# Digital_STMG474RE.net
KiCad netlist of a schematic drawn in Altium Designer
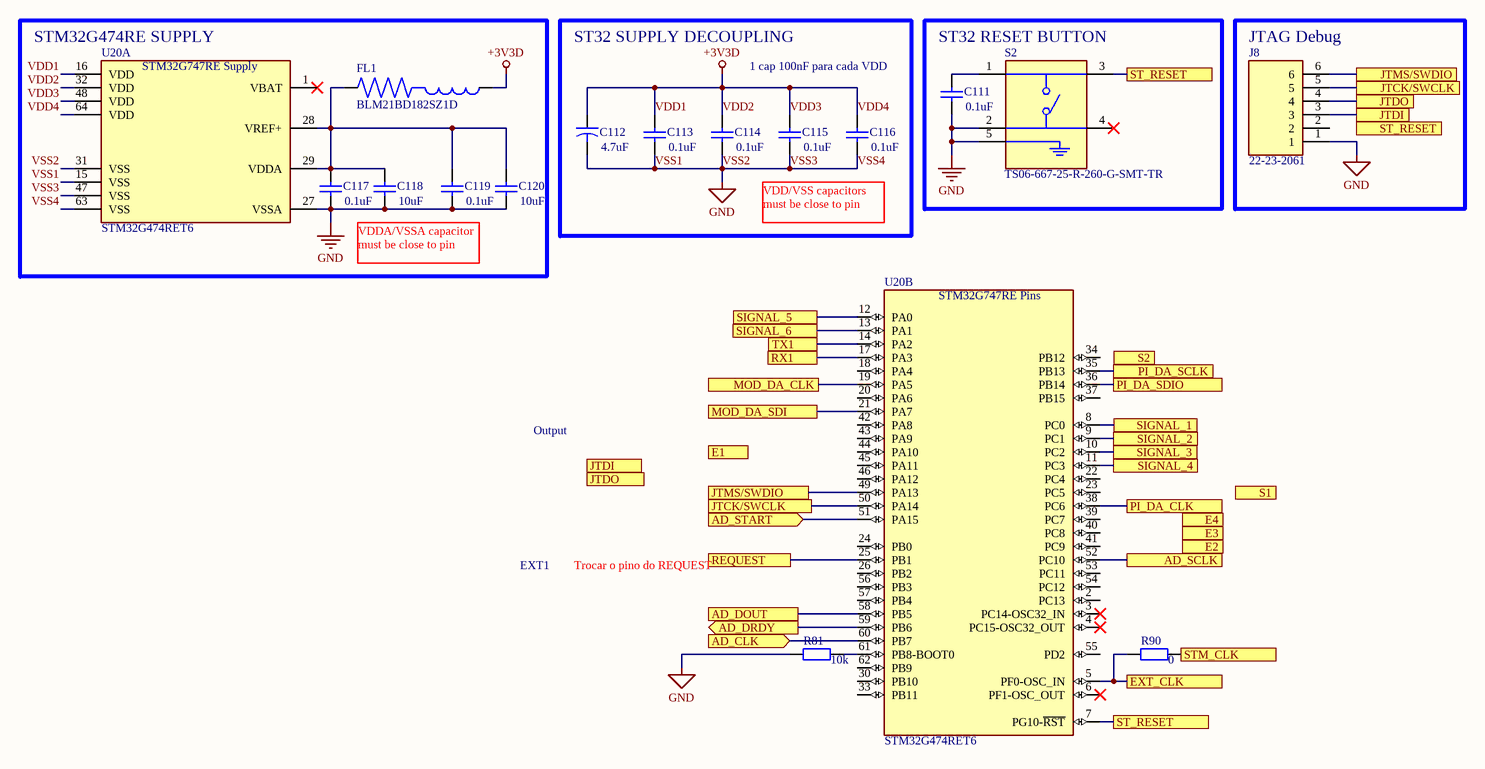
[diagram p0: Digital_STMG474RE.SchDoc]

(export (version "E")
  (design (tool "Eeschema 10.0.6"))
  (components
    (comp (ref "C111")
      (value "0.1uF")
      (footprint "CC_0805")
      (description "Capacitor")
      (fields (field (name "Comment") "Cap") (field (name "PUBLISHER") "Altium Limited"))
      (libsource (lib "Miscellaneous Devices") (part "Cap"))
    )
    (comp (ref "C112")
      (value "4.7uF")
      (footprint "CC_0805")
      (description "Capacitor")
      (fields (field (name "Comment") "Cap2") (field (name "PUBLISHER") "Altium Limited"))
      (libsource (lib "Miscellaneous Devices") (part "Cap2"))
    )
    (comp (ref "C113")
      (value "0.1uF")
      (footprint "CC_0805")
      (description "Capacitor")
      (fields (field (name "Comment") "Cap") (field (name "PUBLISHER") "Altium Limited"))
      (libsource (lib "Miscellaneous Devices") (part "Cap"))
    )
    (comp (ref "C114")
      (value "0.1uF")
      (footprint "CC_0805")
      (description "Capacitor")
      (fields (field (name "Comment") "Cap") (field (name "PUBLISHER") "Altium Limited"))
      (libsource (lib "Miscellaneous Devices") (part "Cap"))
    )
    (comp (ref "C115")
      (value "0.1uF")
      (footprint "CC_0805")
      (description "Capacitor")
      (fields (field (name "Comment") "Cap") (field (name "PUBLISHER") "Altium Limited"))
      (libsource (lib "Miscellaneous Devices") (part "Cap"))
    )
    (comp (ref "C116")
      (value "0.1uF")
      (footprint "CC_0805")
      (description "Capacitor")
      (fields (field (name "Comment") "Cap") (field (name "PUBLISHER") "Altium Limited"))
      (libsource (lib "Miscellaneous Devices") (part "Cap"))
    )
    (comp (ref "C117")
      (value "0.1uF")
      (footprint "CC_0805")
      (description "Capacitor")
      (fields (field (name "Comment") "Cap") (field (name "PUBLISHER") "Altium Limited"))
      (libsource (lib "Miscellaneous Devices") (part "Cap"))
    )
    (comp (ref "C118")
      (value "10uF")
      (footprint "CC_0805")
      (description "Capacitor")
      (fields (field (name "Comment") "Cap") (field (name "PUBLISHER") "Altium Limited"))
      (libsource (lib "Miscellaneous Devices") (part "Cap"))
    )
    (comp (ref "C119")
      (value "0.1uF")
      (footprint "CC_0805")
      (description "Capacitor")
      (fields (field (name "Comment") "Cap") (field (name "PUBLISHER") "Altium Limited"))
      (libsource (lib "Miscellaneous Devices") (part "Cap"))
    )
    (comp (ref "C120")
      (value "10uF")
      (footprint "CC_0805")
      (description "Capacitor")
      (fields (field (name "Comment") "Cap") (field (name "PUBLISHER") "Altium Limited"))
      (libsource (lib "Miscellaneous Devices") (part "Cap"))
    )
    (comp (ref "FL1")
      (value "BLM21BD182SZ1D")
      (footprint "BLM21BD182SZ1D")
      (libsource (lib "Lib_Schematic_Gyro_Single_Axis") (part "BLM21BD182SZ1D"))
    )
    (comp (ref "J8")
      (value "22-23-2061")
      (footprint "22-23-2061")
      (fields (field (name "MOUSER PART NUMBER") "538-22-23-2061"))
      (libsource (lib "Lib_Schematic_Gyro_Single_Axis") (part "22-23-2061"))
    )
    (comp (ref "R81")
      (value "10k")
      (footprint "RR_1220")
      (description "Resistor")
      (fields (field (name "Comment") "Res2") (field (name "PUBLISHER") "Altium Limited"))
      (libsource (lib "Miscellaneous Devices") (part "Res2"))
    )
    (comp (ref "R90")
      (value "0")
      (footprint "RR_1220")
      (description "Resistor")
      (fields (field (name "Comment") "Res2") (field (name "PUBLISHER") "Altium Limited"))
      (libsource (lib "Miscellaneous Devices") (part "Res2"))
    )
    (comp (ref "S2")
      (value "TS06-667-25-R-260-G-SMT-TR")
      (footprint "TS06-667-25-R-260-G-SMT-TR")
      (description "6 x 6.7 mm, 2.5 mm Actuator Height, 260 gf, Red, Surface Mount, SPST, Tactile Switch")
      (fields (field (name "MF") "Same Sky"))
      (libsource (lib "Lib_Schematic_Gyro_Single_Axis") (part "TS06-667-25-R-260-G-SMT-TR"))
    )
    (comp (ref "U20")
      (value "STM32G474RET6")
      (footprint "STMG474RET6")
      (fields (field (name "MF") "STMicroelectronics"))
      (libsource (lib "Lib_Schematic_Gyro_Single_Axis") (part "STM32G474RET6"))
    )
  )
  (nets
    (net (code "1") (name "+3V3D") (class "Default")
      (node (ref "C112") (pin "1") (pinfunction "1_1") (pintype "passive"))
      (node (ref "C113") (pin "2") (pinfunction "2_2") (pintype "passive"))
      (node (ref "C114") (pin "2") (pinfunction "2_2") (pintype "passive"))
      (node (ref "C115") (pin "2") (pinfunction "2_2") (pintype "passive"))
      (node (ref "C116") (pin "2") (pinfunction "2_2") (pintype "passive"))
      (node (ref "FL1") (pin "1") (pinfunction "1_1") (pintype "passive"))
      (node (ref "U20") (pin "16") (pinfunction "VDD_16") (pintype "power_in"))
      (node (ref "U20") (pin "32") (pinfunction "VDD_32") (pintype "power_in"))
      (node (ref "U20") (pin "48") (pinfunction "VDD_48") (pintype "power_in"))
      (node (ref "U20") (pin "64") (pinfunction "VDD_64") (pintype "power_in"))
    )
    (net (code "2") (name "/AD_CLK") (class "Default")
      (node (ref "U20") (pin "60") (pinfunction "PB7_60") (pintype "bidirectional"))
    )
    (net (code "3") (name "/AD_DOUT") (class "Default")
      (node (ref "U20") (pin "58") (pinfunction "PB5_58") (pintype "bidirectional"))
    )
    (net (code "4") (name "/AD_DRDY") (class "Default")
      (node (ref "U20") (pin "59") (pinfunction "PB6_59") (pintype "bidirectional"))
    )
    (net (code "5") (name "/AD_SCLK") (class "Default")
      (node (ref "U20") (pin "52") (pinfunction "PC10_52") (pintype "bidirectional"))
    )
    (net (code "6") (name "/AD_START") (class "Default")
      (node (ref "U20") (pin "51") (pinfunction "PA15_51") (pintype "bidirectional"))
    )
    (net (code "11") (name "/EXT_CLK") (class "Default")
      (node (ref "R90") (pin "1") (pinfunction "1_1") (pintype "passive"))
      (node (ref "U20") (pin "5") (pinfunction "PF0-OSC_IN_5") (pintype "bidirectional"))
    )
    (net (code "12") (name "/JTCK{slash}SWCLK") (class "Default")
      (node (ref "J8") (pin "5") (pinfunction "5_5") (pintype "passive"))
      (node (ref "U20") (pin "50") (pinfunction "PA14_50") (pintype "bidirectional"))
    )
    (net (code "13") (name "/JTDI") (class "Default")
      (node (ref "J8") (pin "3") (pinfunction "3_3") (pintype "passive"))
    )
    (net (code "14") (name "/JTDO") (class "Default")
      (node (ref "J8") (pin "4") (pinfunction "4_4") (pintype "passive"))
    )
    (net (code "15") (name "/JTMS{slash}SWDIO") (class "Default")
      (node (ref "J8") (pin "6") (pinfunction "6_6") (pintype "passive"))
      (node (ref "U20") (pin "49") (pinfunction "PA13_49") (pintype "bidirectional"))
    )
    (net (code "16") (name "/MOD_DA_CLK") (class "Default")
      (node (ref "U20") (pin "19") (pinfunction "PA5_19") (pintype "bidirectional"))
    )
    (net (code "17") (name "/MOD_DA_SDI") (class "Default")
      (node (ref "U20") (pin "21") (pinfunction "PA7_21") (pintype "bidirectional"))
    )
    (net (code "18") (name "/PI_DA_CLK") (class "Default")
      (node (ref "U20") (pin "38") (pinfunction "PC6_38") (pintype "bidirectional"))
    )
    (net (code "19") (name "/PI_DA_SCLK") (class "Default")
      (node (ref "U20") (pin "35") (pinfunction "PB13_35") (pintype "bidirectional"))
    )
    (net (code "20") (name "/PI_DA_SDIO") (class "Default")
      (node (ref "U20") (pin "36") (pinfunction "PB14_36") (pintype "bidirectional"))
    )
    (net (code "21") (name "/REQUEST") (class "Default")
      (node (ref "U20") (pin "25") (pinfunction "PB1_25") (pintype "bidirectional"))
    )
    (net (code "22") (name "/RX1") (class "Default")
      (node (ref "U20") (pin "17") (pinfunction "PA3_17") (pintype "bidirectional"))
    )
    (net (code "25") (name "/SIGNAL_1") (class "Default")
      (node (ref "U20") (pin "8") (pinfunction "PC0_8") (pintype "bidirectional"))
    )
    (net (code "26") (name "/SIGNAL_2") (class "Default")
      (node (ref "U20") (pin "9") (pinfunction "PC1_9") (pintype "bidirectional"))
    )
    (net (code "27") (name "/SIGNAL_3") (class "Default")
      (node (ref "U20") (pin "10") (pinfunction "PC2_10") (pintype "bidirectional"))
    )
    (net (code "28") (name "/SIGNAL_4") (class "Default")
      (node (ref "U20") (pin "11") (pinfunction "PC3_11") (pintype "bidirectional"))
    )
    (net (code "29") (name "/SIGNAL_5") (class "Default")
      (node (ref "U20") (pin "12") (pinfunction "PA0_12") (pintype "bidirectional"))
    )
    (net (code "30") (name "/SIGNAL_6") (class "Default")
      (node (ref "U20") (pin "13") (pinfunction "PA1_13") (pintype "bidirectional"))
    )
    (net (code "31") (name "/STM_CLK") (class "Default")
      (node (ref "R90") (pin "2") (pinfunction "2_2") (pintype "passive"))
    )
    (net (code "32") (name "/ST_RESET") (class "Default")
      (node (ref "S2") (pin "3") (pinfunction "3_3") (pintype "passive"))
      (node (ref "U20") (pin "7") (pinfunction "PG10-~{RST}_7") (pintype "bidirectional"))
    )
    (net (code "33") (name "/TX1") (class "Default")
      (node (ref "U20") (pin "14") (pinfunction "PA2_14") (pintype "bidirectional"))
    )
    (net (code "34") (name "GND") (class "Default")
      (node (ref "C111") (pin "1") (pinfunction "1_1") (pintype "passive"))
      (node (ref "C112") (pin "2") (pinfunction "2_2") (pintype "passive"))
      (node (ref "C113") (pin "1") (pinfunction "1_1") (pintype "passive"))
      (node (ref "C114") (pin "1") (pinfunction "1_1") (pintype "passive"))
      (node (ref "C115") (pin "1") (pinfunction "1_1") (pintype "passive"))
      (node (ref "C116") (pin "1") (pinfunction "1_1") (pintype "passive"))
      (node (ref "C117") (pin "1") (pinfunction "1_1") (pintype "passive"))
      (node (ref "C118") (pin "1") (pinfunction "1_1") (pintype "passive"))
      (node (ref "C119") (pin "1") (pinfunction "1_1") (pintype "passive"))
      (node (ref "C120") (pin "1") (pinfunction "1_1") (pintype "passive"))
      (node (ref "J8") (pin "1") (pinfunction "1_1") (pintype "passive"))
      (node (ref "R81") (pin "1") (pinfunction "1_1") (pintype "passive"))
      (node (ref "S2") (pin "2") (pinfunction "2_2") (pintype "passive"))
      (node (ref "S2") (pin "5") (pinfunction "5_5") (pintype "passive"))
      (node (ref "U20") (pin "15") (pinfunction "VSS_15") (pintype "power_in"))
      (node (ref "U20") (pin "27") (pinfunction "VSSA_27") (pintype "power_in"))
      (node (ref "U20") (pin "31") (pinfunction "VSS_31") (pintype "power_in"))
      (node (ref "U20") (pin "47") (pinfunction "VSS_47") (pintype "power_in"))
      (node (ref "U20") (pin "63") (pinfunction "VSS_63") (pintype "power_in"))
    )
    (net (code "35") (name "Net-(C111-Pad2)") (class "Default")
      (node (ref "C111") (pin "2") (pinfunction "2_2") (pintype "passive"))
      (node (ref "S2") (pin "1") (pinfunction "1_1") (pintype "passive"))
    )
    (net (code "36") (name "Net-(U20A-VDDA)") (class "Default")
      (node (ref "C117") (pin "2") (pinfunction "2_2") (pintype "passive"))
      (node (ref "C118") (pin "2") (pinfunction "2_2") (pintype "passive"))
      (node (ref "C119") (pin "2") (pinfunction "2_2") (pintype "passive"))
      (node (ref "C120") (pin "2") (pinfunction "2_2") (pintype "passive"))
      (node (ref "FL1") (pin "2") (pinfunction "2_2") (pintype "passive"))
      (node (ref "U20") (pin "28") (pinfunction "VREF+_28") (pintype "power_in"))
      (node (ref "U20") (pin "29") (pinfunction "VDDA_29") (pintype "power_in"))
    )
    (net (code "37") (name "Net-(U20B-PB8-BOOT0)") (class "Default")
      (node (ref "R81") (pin "2") (pinfunction "2_2") (pintype "passive"))
      (node (ref "U20") (pin "61") (pinfunction "PB8-BOOT0_61") (pintype "bidirectional"))
    )
    (net (code "38") (name "unconnected-(J8-Pad2)") (class "Default")
      (node (ref "J8") (pin "2") (pinfunction "2_2") (pintype "passive"))
    )
    (net (code "39") (name "unconnected-(S2-Pad4)") (class "Default")
      (node (ref "S2") (pin "4") (pinfunction "4_4") (pintype "passive+no_connect"))
    )
    (net (code "40") (name "unconnected-(U20A-VBAT-Pad1)") (class "Default")
      (node (ref "U20") (pin "1") (pinfunction "VBAT_1") (pintype "power_in+no_connect"))
    )
    (net (code "41") (name "unconnected-(U20B-PA4-Pad18)") (class "Default")
      (node (ref "U20") (pin "18") (pinfunction "PA4_18") (pintype "bidirectional"))
    )
    (net (code "42") (name "unconnected-(U20B-PA6-Pad20)") (class "Default")
      (node (ref "U20") (pin "20") (pinfunction "PA6_20") (pintype "bidirectional"))
    )
    (net (code "43") (name "unconnected-(U20B-PA8-Pad42)") (class "Default")
      (node (ref "U20") (pin "42") (pinfunction "PA8_42") (pintype "bidirectional"))
    )
    (net (code "44") (name "unconnected-(U20B-PA9-Pad43)") (class "Default")
      (node (ref "U20") (pin "43") (pinfunction "PA9_43") (pintype "bidirectional"))
    )
    (net (code "45") (name "unconnected-(U20B-PA10-Pad44)") (class "Default")
      (node (ref "U20") (pin "44") (pinfunction "PA10_44") (pintype "bidirectional"))
    )
    (net (code "46") (name "unconnected-(U20B-PA11-Pad45)") (class "Default")
      (node (ref "U20") (pin "45") (pinfunction "PA11_45") (pintype "bidirectional"))
    )
    (net (code "47") (name "unconnected-(U20B-PA12-Pad46)") (class "Default")
      (node (ref "U20") (pin "46") (pinfunction "PA12_46") (pintype "bidirectional"))
    )
    (net (code "48") (name "unconnected-(U20B-PB0-Pad24)") (class "Default")
      (node (ref "U20") (pin "24") (pinfunction "PB0_24") (pintype "bidirectional"))
    )
    (net (code "49") (name "unconnected-(U20B-PB2-Pad26)") (class "Default")
      (node (ref "U20") (pin "26") (pinfunction "PB2_26") (pintype "bidirectional"))
    )
    (net (code "50") (name "unconnected-(U20B-PB3-Pad56)") (class "Default")
      (node (ref "U20") (pin "56") (pinfunction "PB3_56") (pintype "bidirectional"))
    )
    (net (code "51") (name "unconnected-(U20B-PB4-Pad57)") (class "Default")
      (node (ref "U20") (pin "57") (pinfunction "PB4_57") (pintype "bidirectional"))
    )
    (net (code "52") (name "unconnected-(U20B-PB9-Pad62)") (class "Default")
      (node (ref "U20") (pin "62") (pinfunction "PB9_62") (pintype "bidirectional"))
    )
    (net (code "53") (name "unconnected-(U20B-PB10-Pad30)") (class "Default")
      (node (ref "U20") (pin "30") (pinfunction "PB10_30") (pintype "bidirectional"))
    )
    (net (code "54") (name "unconnected-(U20B-PB11-Pad33)") (class "Default")
      (node (ref "U20") (pin "33") (pinfunction "PB11_33") (pintype "bidirectional"))
    )
    (net (code "55") (name "unconnected-(U20B-PB12-Pad34)") (class "Default")
      (node (ref "U20") (pin "34") (pinfunction "PB12_34") (pintype "bidirectional"))
    )
    (net (code "56") (name "unconnected-(U20B-PB15-Pad37)") (class "Default")
      (node (ref "U20") (pin "37") (pinfunction "PB15_37") (pintype "bidirectional"))
    )
    (net (code "57") (name "unconnected-(U20B-PC4-Pad22)") (class "Default")
      (node (ref "U20") (pin "22") (pinfunction "PC4_22") (pintype "bidirectional"))
    )
    (net (code "58") (name "unconnected-(U20B-PC5-Pad23)") (class "Default")
      (node (ref "U20") (pin "23") (pinfunction "PC5_23") (pintype "bidirectional"))
    )
    (net (code "59") (name "unconnected-(U20B-PC7-Pad39)") (class "Default")
      (node (ref "U20") (pin "39") (pinfunction "PC7_39") (pintype "bidirectional"))
    )
    (net (code "60") (name "unconnected-(U20B-PC8-Pad40)") (class "Default")
      (node (ref "U20") (pin "40") (pinfunction "PC8_40") (pintype "bidirectional"))
    )
    (net (code "61") (name "unconnected-(U20B-PC9-Pad41)") (class "Default")
      (node (ref "U20") (pin "41") (pinfunction "PC9_41") (pintype "bidirectional"))
    )
    (net (code "62") (name "unconnected-(U20B-PC11-Pad53)") (class "Default")
      (node (ref "U20") (pin "53") (pinfunction "PC11_53") (pintype "bidirectional"))
    )
    (net (code "63") (name "unconnected-(U20B-PC12-Pad54)") (class "Default")
      (node (ref "U20") (pin "54") (pinfunction "PC12_54") (pintype "bidirectional"))
    )
    (net (code "64") (name "unconnected-(U20B-PC13-Pad2)") (class "Default")
      (node (ref "U20") (pin "2") (pinfunction "PC13_2") (pintype "bidirectional"))
    )
    (net (code "65") (name "unconnected-(U20B-PC14-OSC32_IN-Pad3)") (class "Default")
      (node (ref "U20") (pin "3") (pinfunction "PC14-OSC32_IN_3") (pintype "bidirectional+no_connect"))
    )
    (net (code "66") (name "unconnected-(U20B-PC15-OSC32_OUT-Pad4)") (class "Default")
      (node (ref "U20") (pin "4") (pinfunction "PC15-OSC32_OUT_4") (pintype "bidirectional+no_connect"))
    )
    (net (code "67") (name "unconnected-(U20B-PD2-Pad55)") (class "Default")
      (node (ref "U20") (pin "55") (pinfunction "PD2_55") (pintype "bidirectional"))
    )
    (net (code "68") (name "unconnected-(U20B-PF1-OSC_OUT-Pad6)") (class "Default")
      (node (ref "U20") (pin "6") (pinfunction "PF1-OSC_OUT_6") (pintype "bidirectional+no_connect"))
    )
  )
)
